# RegulatorPower.net
KiCad netlist of a schematic drawn in Altium Designer
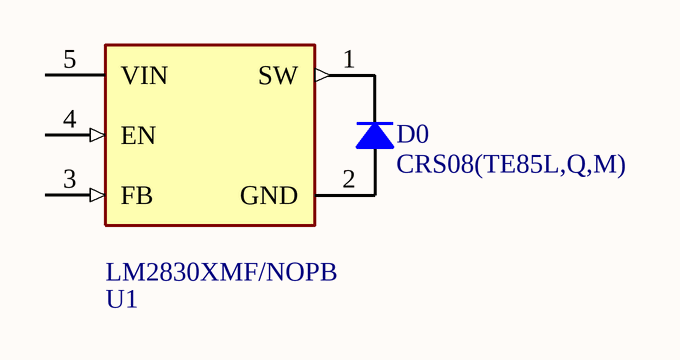
[diagram p0: RegulatorPower.SchDoc]

(export (version "E")
  (design (tool "Eeschema 10.0.6"))
  (components
    (comp (ref "D0")
      (value "CRS08(TE85L,Q,M)")
      (footprint "SOD123F")
      (description "DIODE SCHOTTKY 30V 1.5A SFLAT")
      (fields (field (name "MANUFACTURER") "Toshiba Semiconductor and Storage"))
      (libsource (lib "Celestial Altium Library - altium_library") (part "Diode"))
    )
    (comp (ref "U1")
      (value "LM2830XMF-NOPB")
      (fields (field (name "PART NUMBER") "LM2830XMF/NOPB"))
      (libsource (lib "IC_Texas Instruments_LM2830XMF_NOPB") (part "LM2830XMF-NOPB"))
    )
  )
  (nets
    (net (code "1") (name "Net-(U1-GND)") (class "Default")
      (node (ref "D0") (pin "1") (pinfunction "1_1") (pintype "passive"))
      (node (ref "U1") (pin "2") (pinfunction "GND_2") (pintype "power_in"))
    )
    (net (code "2") (name "Net-(U1-SW)") (class "Default")
      (node (ref "D0") (pin "2") (pinfunction "2_2") (pintype "passive"))
      (node (ref "U1") (pin "1") (pinfunction "SW_1") (pintype "output"))
    )
    (net (code "3") (name "unconnected-(U1-EN-Pad4)") (class "Default")
      (node (ref "U1") (pin "4") (pinfunction "EN_4") (pintype "input"))
    )
    (net (code "4") (name "unconnected-(U1-FB-Pad3)") (class "Default")
      (node (ref "U1") (pin "3") (pinfunction "FB_3") (pintype "input"))
    )
    (net (code "5") (name "unconnected-(U1-VIN-Pad5)") (class "Default")
      (node (ref "U1") (pin "5") (pinfunction "VIN_5") (pintype "power_in"))
    )
  )
)
